# State.net
KiCad netlist of a schematic drawn in Altium Designer
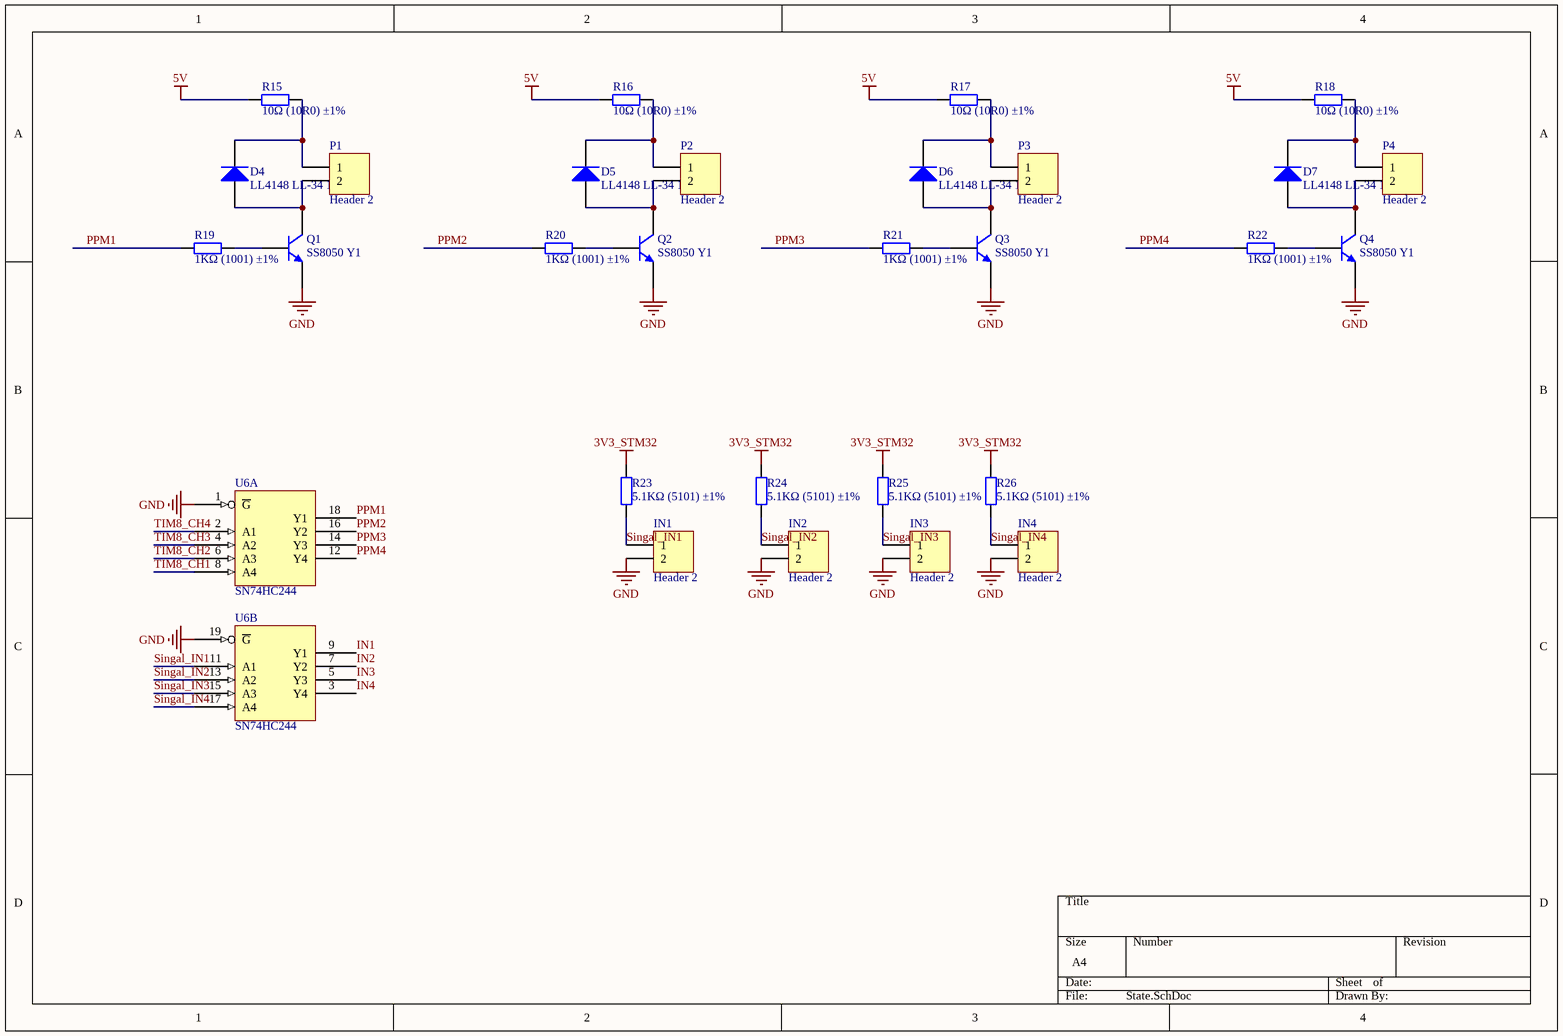
[diagram p0: State.SchDoc]

(export (version "E")
  (design (tool "Eeschema 10.0.6"))
  (components
    (comp (ref "D4")
      (value "LL4148 LL-34 1206")
      (footprint "LL-34")
      (description "开关二极管")
      (libsource (lib "Miscellaneous Devices LC") (part "LL-34 LL4148 LL-34 1206"))
    )
    (comp (ref "D5")
      (value "LL4148 LL-34 1206")
      (footprint "LL-34")
      (description "开关二极管")
      (libsource (lib "Miscellaneous Devices LC") (part "LL-34 LL4148 LL-34 1206"))
    )
    (comp (ref "D6")
      (value "LL4148 LL-34 1206")
      (footprint "LL-34")
      (description "开关二极管")
      (libsource (lib "Miscellaneous Devices LC") (part "LL-34 LL4148 LL-34 1206"))
    )
    (comp (ref "D7")
      (value "LL4148 LL-34 1206")
      (footprint "LL-34")
      (description "开关二极管")
      (libsource (lib "Miscellaneous Devices LC") (part "LL-34 LL4148 LL-34 1206"))
    )
    (comp (ref "IN1")
      (value "Header 2")
      (footprint "XH2.54_2P")
      (description "Header, 2-Pin")
      (fields (field (name "PUBLISHER") "Altium Limited"))
      (libsource (lib "Miscellaneous Connectors") (part "Header 2"))
    )
    (comp (ref "IN2")
      (value "Header 2")
      (footprint "XH2.54_2P")
      (description "Header, 2-Pin")
      (fields (field (name "PUBLISHER") "Altium Limited"))
      (libsource (lib "Miscellaneous Connectors") (part "Header 2"))
    )
    (comp (ref "IN3")
      (value "Header 2")
      (footprint "XH2.54_2P")
      (description "Header, 2-Pin")
      (fields (field (name "PUBLISHER") "Altium Limited"))
      (libsource (lib "Miscellaneous Connectors") (part "Header 2"))
    )
    (comp (ref "IN4")
      (value "Header 2")
      (footprint "XH2.54_2P")
      (description "Header, 2-Pin")
      (fields (field (name "PUBLISHER") "Altium Limited"))
      (libsource (lib "Miscellaneous Connectors") (part "Header 2"))
    )
    (comp (ref "P1")
      (value "Header 2")
      (footprint "XH2.54_2P")
      (description "Header, 2-Pin")
      (fields (field (name "PUBLISHER") "Altium Limited"))
      (libsource (lib "Miscellaneous Connectors") (part "Header 2"))
    )
    (comp (ref "P2")
      (value "Header 2")
      (footprint "XH2.54_2P")
      (description "Header, 2-Pin")
      (fields (field (name "PUBLISHER") "Altium Limited"))
      (libsource (lib "Miscellaneous Connectors") (part "Header 2"))
    )
    (comp (ref "P3")
      (value "Header 2")
      (footprint "XH2.54_2P")
      (description "Header, 2-Pin")
      (fields (field (name "PUBLISHER") "Altium Limited"))
      (libsource (lib "Miscellaneous Connectors") (part "Header 2"))
    )
    (comp (ref "P4")
      (value "Header 2")
      (footprint "XH2.54_2P")
      (description "Header, 2-Pin")
      (fields (field (name "PUBLISHER") "Altium Limited"))
      (libsource (lib "Miscellaneous Connectors") (part "Header 2"))
    )
    (comp (ref "Q1")
      (value "SS8050 Y1")
      (footprint "SOT-23(SOT-23-3)")
      (description "三极管")
      (libsource (lib "Miscellaneous Devices LC") (part "SOT-23 SS8050 Y1"))
    )
    (comp (ref "Q2")
      (value "SS8050 Y1")
      (footprint "SOT-23(SOT-23-3)")
      (description "三极管")
      (libsource (lib "Miscellaneous Devices LC") (part "SOT-23 SS8050 Y1"))
    )
    (comp (ref "Q3")
      (value "SS8050 Y1")
      (footprint "SOT-23(SOT-23-3)")
      (description "三极管")
      (libsource (lib "Miscellaneous Devices LC") (part "SOT-23 SS8050 Y1"))
    )
    (comp (ref "Q4")
      (value "SS8050 Y1")
      (footprint "SOT-23(SOT-23-3)")
      (description "三极管")
      (libsource (lib "Miscellaneous Devices LC") (part "SOT-23 SS8050 Y1"))
    )
    (comp (ref "R15")
      (value "10Ω (10R0) ±1%")
      (footprint "1206_R")
      (description "贴片电阻")
      (libsource (lib "Miscellaneous Devices LC") (part "1206 10Ω (10R0) 1%"))
    )
    (comp (ref "R16")
      (value "10Ω (10R0) ±1%")
      (footprint "1206_R")
      (description "贴片电阻")
      (libsource (lib "Miscellaneous Devices LC") (part "1206 10Ω (10R0) 1%"))
    )
    (comp (ref "R17")
      (value "10Ω (10R0) ±1%")
      (footprint "1206_R")
      (description "贴片电阻")
      (libsource (lib "Miscellaneous Devices LC") (part "1206 10Ω (10R0) 1%"))
    )
    (comp (ref "R18")
      (value "10Ω (10R0) ±1%")
      (footprint "1206_R")
      (description "贴片电阻")
      (libsource (lib "Miscellaneous Devices LC") (part "1206 10Ω (10R0) 1%"))
    )
    (comp (ref "R19")
      (value "1KΩ (1001) ±1%")
      (footprint "0603_R")
      (description "贴片电阻")
      (libsource (lib "Miscellaneous Devices LC") (part "0603 1KΩ (1001) 1%"))
    )
    (comp (ref "R20")
      (value "1KΩ (1001) ±1%")
      (footprint "0603_R")
      (description "贴片电阻")
      (libsource (lib "Miscellaneous Devices LC") (part "0603 1KΩ (1001) 1%"))
    )
    (comp (ref "R21")
      (value "1KΩ (1001) ±1%")
      (footprint "0603_R")
      (description "贴片电阻")
      (libsource (lib "Miscellaneous Devices LC") (part "0603 1KΩ (1001) 1%"))
    )
    (comp (ref "R22")
      (value "1KΩ (1001) ±1%")
      (footprint "0603_R")
      (description "贴片电阻")
      (libsource (lib "Miscellaneous Devices LC") (part "0603 1KΩ (1001) 1%"))
    )
    (comp (ref "R23")
      (value "5.1KΩ (5101) ±1%")
      (footprint "LC-0603_R")
      (description "贴片电阻")
      (libsource (lib "Miscellaneous Devices LC") (part "0603 5.1KΩ (5101) 1%"))
    )
    (comp (ref "R24")
      (value "5.1KΩ (5101) ±1%")
      (footprint "LC-0603_R")
      (description "贴片电阻")
      (libsource (lib "Miscellaneous Devices LC") (part "0603 5.1KΩ (5101) 1%"))
    )
    (comp (ref "R25")
      (value "5.1KΩ (5101) ±1%")
      (footprint "LC-0603_R")
      (description "贴片电阻")
      (libsource (lib "Miscellaneous Devices LC") (part "0603 5.1KΩ (5101) 1%"))
    )
    (comp (ref "R26")
      (value "5.1KΩ (5101) ±1%")
      (footprint "LC-0603_R")
      (description "贴片电阻")
      (libsource (lib "Miscellaneous Devices LC") (part "0603 5.1KΩ (5101) 1%"))
    )
    (comp (ref "U6")
      (value "SN74HC244")
      (footprint "SOIC-20_300mil")
      (description "OCTAL BUF AND LIN DRV 3SO")
      (libsource (lib "CMOS&TTL74") (part "SN74HC244"))
    )
  )
  (nets
    (net (code "1") (name "/IN1") (class "Default")
      (node (ref "U6") (pin "9") (pinfunction "Y1_9") (pintype "tri_state"))
    )
    (net (code "2") (name "/IN2") (class "Default")
      (node (ref "U6") (pin "7") (pinfunction "Y2_7") (pintype "tri_state"))
    )
    (net (code "3") (name "/IN3") (class "Default")
      (node (ref "U6") (pin "5") (pinfunction "Y3_5") (pintype "tri_state"))
    )
    (net (code "4") (name "/IN4") (class "Default")
      (node (ref "U6") (pin "3") (pinfunction "Y4_3") (pintype "tri_state"))
    )
    (net (code "5") (name "/PPM1") (class "Default")
      (node (ref "R19") (pin "1") (pinfunction "1_1") (pintype "passive"))
      (node (ref "U6") (pin "18") (pinfunction "Y1_18") (pintype "tri_state"))
    )
    (net (code "6") (name "/PPM2") (class "Default")
      (node (ref "R20") (pin "1") (pinfunction "1_1") (pintype "passive"))
      (node (ref "U6") (pin "16") (pinfunction "Y2_16") (pintype "tri_state"))
    )
    (net (code "7") (name "/PPM3") (class "Default")
      (node (ref "R21") (pin "1") (pinfunction "1_1") (pintype "passive"))
      (node (ref "U6") (pin "14") (pinfunction "Y3_14") (pintype "tri_state"))
    )
    (net (code "8") (name "/PPM4") (class "Default")
      (node (ref "R22") (pin "1") (pinfunction "1_1") (pintype "passive"))
      (node (ref "U6") (pin "12") (pinfunction "Y4_12") (pintype "tri_state"))
    )
    (net (code "9") (name "/Singal_IN1") (class "Default")
      (node (ref "IN1") (pin "1") (pinfunction "1_1") (pintype "passive"))
      (node (ref "R23") (pin "1") (pinfunction "1_1") (pintype "passive"))
      (node (ref "U6") (pin "11") (pinfunction "A1_11") (pintype "input"))
    )
    (net (code "10") (name "/Singal_IN2") (class "Default")
      (node (ref "IN2") (pin "1") (pinfunction "1_1") (pintype "passive"))
      (node (ref "R24") (pin "1") (pinfunction "1_1") (pintype "passive"))
      (node (ref "U6") (pin "13") (pinfunction "A2_13") (pintype "input"))
    )
    (net (code "11") (name "/Singal_IN3") (class "Default")
      (node (ref "IN3") (pin "1") (pinfunction "1_1") (pintype "passive"))
      (node (ref "R25") (pin "1") (pinfunction "1_1") (pintype "passive"))
      (node (ref "U6") (pin "15") (pinfunction "A3_15") (pintype "input"))
    )
    (net (code "12") (name "/Singal_IN4") (class "Default")
      (node (ref "IN4") (pin "1") (pinfunction "1_1") (pintype "passive"))
      (node (ref "R26") (pin "1") (pinfunction "1_1") (pintype "passive"))
      (node (ref "U6") (pin "17") (pinfunction "A4_17") (pintype "input"))
    )
    (net (code "13") (name "/TIM8_CH1") (class "Default")
      (node (ref "U6") (pin "8") (pinfunction "A4_8") (pintype "input"))
    )
    (net (code "14") (name "/TIM8_CH2") (class "Default")
      (node (ref "U6") (pin "6") (pinfunction "A3_6") (pintype "input"))
    )
    (net (code "15") (name "/TIM8_CH3") (class "Default")
      (node (ref "U6") (pin "4") (pinfunction "A2_4") (pintype "input"))
    )
    (net (code "16") (name "/TIM8_CH4") (class "Default")
      (node (ref "U6") (pin "2") (pinfunction "A1_2") (pintype "input"))
    )
    (net (code "17") (name "3V3_STM32") (class "Default")
      (node (ref "R23") (pin "2") (pinfunction "2_2") (pintype "passive"))
      (node (ref "R24") (pin "2") (pinfunction "2_2") (pintype "passive"))
      (node (ref "R25") (pin "2") (pinfunction "2_2") (pintype "passive"))
      (node (ref "R26") (pin "2") (pinfunction "2_2") (pintype "passive"))
    )
    (net (code "18") (name "5V") (class "Default")
      (node (ref "R15") (pin "2") (pinfunction "2_2") (pintype "passive"))
      (node (ref "R16") (pin "2") (pinfunction "2_2") (pintype "passive"))
      (node (ref "R17") (pin "2") (pinfunction "2_2") (pintype "passive"))
      (node (ref "R18") (pin "2") (pinfunction "2_2") (pintype "passive"))
    )
    (net (code "19") (name "GND") (class "Default")
      (node (ref "IN1") (pin "2") (pinfunction "2_2") (pintype "passive"))
      (node (ref "IN2") (pin "2") (pinfunction "2_2") (pintype "passive"))
      (node (ref "IN3") (pin "2") (pinfunction "2_2") (pintype "passive"))
      (node (ref "IN4") (pin "2") (pinfunction "2_2") (pintype "passive"))
      (node (ref "Q1") (pin "2") (pinfunction "E_2") (pintype "passive"))
      (node (ref "Q2") (pin "2") (pinfunction "E_2") (pintype "passive"))
      (node (ref "Q3") (pin "2") (pinfunction "E_2") (pintype "passive"))
      (node (ref "Q4") (pin "2") (pinfunction "E_2") (pintype "passive"))
      (node (ref "U6") (pin "1") (pinfunction "~{G}_1") (pintype "input"))
      (node (ref "U6") (pin "10") (pinfunction "GND_10") (pintype "power_in"))
      (node (ref "U6") (pin "19") (pinfunction "~{G}_19") (pintype "input"))
    )
    (net (code "20") (name "Net-(D4-A)") (class "Default")
      (node (ref "D4") (pin "1") (pinfunction "A_1") (pintype "passive"))
      (node (ref "P1") (pin "2") (pinfunction "2_2") (pintype "passive"))
      (node (ref "Q1") (pin "3") (pinfunction "C_3") (pintype "passive"))
    )
    (net (code "21") (name "Net-(D4-K)") (class "Default")
      (node (ref "D4") (pin "2") (pinfunction "K_2") (pintype "passive"))
      (node (ref "P1") (pin "1") (pinfunction "1_1") (pintype "passive"))
      (node (ref "R15") (pin "1") (pinfunction "1_1") (pintype "passive"))
    )
    (net (code "22") (name "Net-(D5-A)") (class "Default")
      (node (ref "D5") (pin "1") (pinfunction "A_1") (pintype "passive"))
      (node (ref "P2") (pin "2") (pinfunction "2_2") (pintype "passive"))
      (node (ref "Q2") (pin "3") (pinfunction "C_3") (pintype "passive"))
    )
    (net (code "23") (name "Net-(D5-K)") (class "Default")
      (node (ref "D5") (pin "2") (pinfunction "K_2") (pintype "passive"))
      (node (ref "P2") (pin "1") (pinfunction "1_1") (pintype "passive"))
      (node (ref "R16") (pin "1") (pinfunction "1_1") (pintype "passive"))
    )
    (net (code "24") (name "Net-(D6-A)") (class "Default")
      (node (ref "D6") (pin "1") (pinfunction "A_1") (pintype "passive"))
      (node (ref "P3") (pin "2") (pinfunction "2_2") (pintype "passive"))
      (node (ref "Q3") (pin "3") (pinfunction "C_3") (pintype "passive"))
    )
    (net (code "25") (name "Net-(D6-K)") (class "Default")
      (node (ref "D6") (pin "2") (pinfunction "K_2") (pintype "passive"))
      (node (ref "P3") (pin "1") (pinfunction "1_1") (pintype "passive"))
      (node (ref "R17") (pin "1") (pinfunction "1_1") (pintype "passive"))
    )
    (net (code "26") (name "Net-(D7-A)") (class "Default")
      (node (ref "D7") (pin "1") (pinfunction "A_1") (pintype "passive"))
      (node (ref "P4") (pin "2") (pinfunction "2_2") (pintype "passive"))
      (node (ref "Q4") (pin "3") (pinfunction "C_3") (pintype "passive"))
    )
    (net (code "27") (name "Net-(D7-K)") (class "Default")
      (node (ref "D7") (pin "2") (pinfunction "K_2") (pintype "passive"))
      (node (ref "P4") (pin "1") (pinfunction "1_1") (pintype "passive"))
      (node (ref "R18") (pin "1") (pinfunction "1_1") (pintype "passive"))
    )
    (net (code "28") (name "Net-(Q1-B)") (class "Default")
      (node (ref "Q1") (pin "1") (pinfunction "B_1") (pintype "passive"))
      (node (ref "R19") (pin "2") (pinfunction "2_2") (pintype "passive"))
    )
    (net (code "29") (name "Net-(Q2-B)") (class "Default")
      (node (ref "Q2") (pin "1") (pinfunction "B_1") (pintype "passive"))
      (node (ref "R20") (pin "2") (pinfunction "2_2") (pintype "passive"))
    )
    (net (code "30") (name "Net-(Q3-B)") (class "Default")
      (node (ref "Q3") (pin "1") (pinfunction "B_1") (pintype "passive"))
      (node (ref "R21") (pin "2") (pinfunction "2_2") (pintype "passive"))
    )
    (net (code "31") (name "Net-(Q4-B)") (class "Default")
      (node (ref "Q4") (pin "1") (pinfunction "B_1") (pintype "passive"))
      (node (ref "R22") (pin "2") (pinfunction "2_2") (pintype "passive"))
    )
    (net (code "32") (name "VCC") (class "Default")
      (node (ref "U6") (pin "20") (pinfunction "VCC_20") (pintype "power_in"))
    )
  )
)
